# SH09-PWR2.net
KiCad netlist of a schematic drawn in Altium Designer
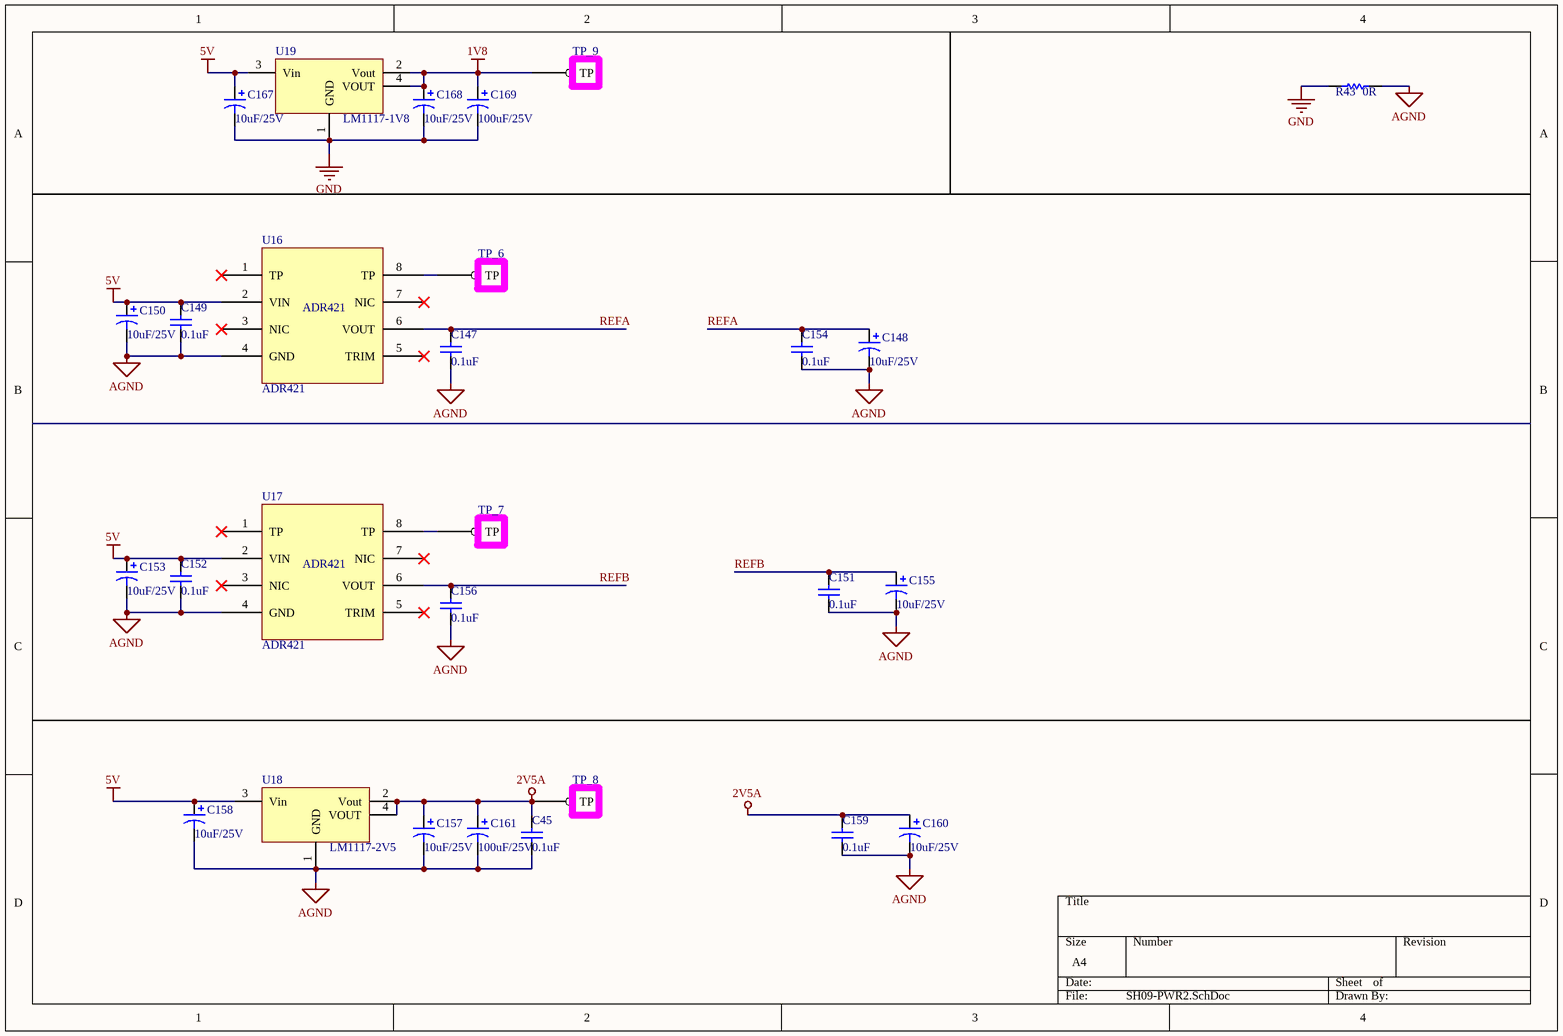
[diagram p0: SH09-PWR2.SchDoc]

(export (version "E")
  (design (tool "Eeschema 10.0.6"))
  (components
    (comp (ref "C45")
      (value "0.1uF")
      (footprint "1608[0603]")
      (description "Capacitor")
      (fields (field (name "Comment") "Cap,0.1uF/0603") (field (name "PUBLISHER") "Altium Limited"))
      (libsource (lib "Miscellaneous Devices") (part "Cap"))
    )
    (comp (ref "C147")
      (value "0.1uF")
      (footprint "1608[0603]")
      (description "Capacitor")
      (fields (field (name "Comment") "Cap,0.1uF/0603") (field (name "PUBLISHER") "Altium Limited"))
      (libsource (lib "Miscellaneous Devices") (part "Cap"))
    )
    (comp (ref "C148")
      (value "10uF/25V")
      (footprint "1206[3216]")
      (description "Polarized Capacitor (Radial)")
      (fields (field (name "Comment") "Cap Pol,10uF/25V,1206") (field (name "PUBLISHER") "Altium Limited"))
      (libsource (lib "Miscellaneous Devices") (part "Cap Pol1"))
    )
    (comp (ref "C149")
      (value "0.1uF")
      (footprint "1608[0603]")
      (description "Capacitor")
      (fields (field (name "Comment") "Cap,0.1uF/0603") (field (name "PUBLISHER") "Altium Limited"))
      (libsource (lib "Miscellaneous Devices") (part "Cap"))
    )
    (comp (ref "C150")
      (value "10uF/25V")
      (footprint "1206[3216]")
      (description "Polarized Capacitor (Radial)")
      (fields (field (name "Comment") "Cap Pol,10uF/25V,1206") (field (name "PUBLISHER") "Altium Limited"))
      (libsource (lib "Miscellaneous Devices") (part "Cap Pol1"))
    )
    (comp (ref "C151")
      (value "0.1uF")
      (footprint "1608[0603]")
      (description "Capacitor")
      (fields (field (name "Comment") "Cap,0.1uF/0603") (field (name "PUBLISHER") "Altium Limited"))
      (libsource (lib "Miscellaneous Devices") (part "Cap"))
    )
    (comp (ref "C152")
      (value "0.1uF")
      (footprint "1608[0603]")
      (description "Capacitor")
      (fields (field (name "Comment") "Cap,0.1uF/0603") (field (name "PUBLISHER") "Altium Limited"))
      (libsource (lib "Miscellaneous Devices") (part "Cap"))
    )
    (comp (ref "C153")
      (value "10uF/25V")
      (footprint "1206[3216]")
      (description "Polarized Capacitor (Radial)")
      (fields (field (name "Comment") "Cap Pol,10uF/25V,1206") (field (name "PUBLISHER") "Altium Limited"))
      (libsource (lib "Miscellaneous Devices") (part "Cap Pol1"))
    )
    (comp (ref "C154")
      (value "0.1uF")
      (footprint "1608[0603]")
      (description "Capacitor")
      (fields (field (name "Comment") "Cap,0.1uF/0603") (field (name "PUBLISHER") "Altium Limited"))
      (libsource (lib "Miscellaneous Devices") (part "Cap"))
    )
    (comp (ref "C155")
      (value "10uF/25V")
      (footprint "1206[3216]")
      (description "Polarized Capacitor (Radial)")
      (fields (field (name "Comment") "Cap Pol,10uF/25V,1206") (field (name "PUBLISHER") "Altium Limited"))
      (libsource (lib "Miscellaneous Devices") (part "Cap Pol1"))
    )
    (comp (ref "C156")
      (value "0.1uF")
      (footprint "1608[0603]")
      (description "Capacitor")
      (fields (field (name "Comment") "Cap,0.1uF/0603") (field (name "PUBLISHER") "Altium Limited"))
      (libsource (lib "Miscellaneous Devices") (part "Cap"))
    )
    (comp (ref "C157")
      (value "10uF/25V")
      (footprint "1206[3216]")
      (description "Polarized Capacitor (Radial)")
      (fields (field (name "Comment") "Cap Pol,10uF/25V,1206") (field (name "PUBLISHER") "Altium Limited"))
      (libsource (lib "Miscellaneous Devices") (part "Cap Pol1"))
    )
    (comp (ref "C158")
      (value "10uF/25V")
      (footprint "1206[3216]")
      (description "Polarized Capacitor (Radial)")
      (fields (field (name "Comment") "Cap Pol,10uF/25V,1206") (field (name "PUBLISHER") "Altium Limited"))
      (libsource (lib "Miscellaneous Devices") (part "Cap Pol1"))
    )
    (comp (ref "C159")
      (value "0.1uF")
      (footprint "1608[0603]")
      (description "Capacitor")
      (fields (field (name "Comment") "Cap,0.1uF/0603") (field (name "PUBLISHER") "Altium Limited"))
      (libsource (lib "Miscellaneous Devices") (part "Cap"))
    )
    (comp (ref "C160")
      (value "10uF/25V")
      (footprint "1206[3216]")
      (description "Polarized Capacitor (Radial)")
      (fields (field (name "Comment") "Cap Pol,10uF/25V,1206") (field (name "PUBLISHER") "Altium Limited"))
      (libsource (lib "Miscellaneous Devices") (part "Cap Pol1"))
    )
    (comp (ref "C161")
      (value "100uF/25V")
      (footprint "1210[3528]")
      (description "Polarized Capacitor (Radial)")
      (fields (field (name "Comment") "Cap Pol,100uF/25V,1210") (field (name "PUBLISHER") "Altium Limited"))
      (libsource (lib "Miscellaneous Devices") (part "Cap Pol1"))
    )
    (comp (ref "C167")
      (value "10uF/25V")
      (footprint "1206[3216]")
      (description "Polarized Capacitor (Radial)")
      (fields (field (name "Comment") "Cap Pol,10uF/25V,1206") (field (name "PUBLISHER") "Altium Limited"))
      (libsource (lib "Miscellaneous Devices") (part "Cap Pol1"))
    )
    (comp (ref "C168")
      (value "10uF/25V")
      (footprint "1206[3216]")
      (description "Polarized Capacitor (Radial)")
      (fields (field (name "Comment") "Cap Pol,10uF/25V,1206") (field (name "PUBLISHER") "Altium Limited"))
      (libsource (lib "Miscellaneous Devices") (part "Cap Pol1"))
    )
    (comp (ref "C169")
      (value "100uF/25V")
      (footprint "1210[3528]")
      (description "Polarized Capacitor (Radial)")
      (fields (field (name "Comment") "Cap Pol,100uF/25V,1210") (field (name "PUBLISHER") "Altium Limited"))
      (libsource (lib "Miscellaneous Devices") (part "Cap Pol1"))
    )
    (comp (ref "R43")
      (value "0R")
      (footprint "Laser-LiuXin:2012[0805]")
      (description "Resistor")
      (fields (field (name "Comment") "Res,0R/0805") (field (name "PUBLISHER") "Altium Limited"))
      (libsource (lib "Miscellaneous Devices") (part "Res1"))
    )
    (comp (ref "TP_6") (value "REFA") (footprint "MYTP") (libsource (lib "*") (part "TEST POINT_0")))
    (comp (ref "TP_7") (value "REFB") (footprint "MYTP") (libsource (lib "*") (part "TEST POINT_0")))
    (comp (ref "TP_8") (value "2V5") (footprint "MYTP") (libsource (lib "*") (part "TEST POINT_0")))
    (comp (ref "TP_9") (value "1V8") (footprint "MYTP") (libsource (lib "*") (part "TEST POINT_0")))
    (comp (ref "U16")
      (value "ADR421")
      (footprint "SOIC127P600X175-8N")
      (description "Ultraprecision Low Noise, 2.048 V/2.500 V/  3.00 V/5.00 V XFET? Voltage References")
      (libsource (lib "Laser-LiuXin") (part "PWR_ADR421"))
    )
    (comp (ref "U17")
      (value "ADR421")
      (footprint "SOIC127P600X175-8N")
      (description "Ultraprecision Low Noise, 2.048 V/2.500 V/  3.00 V/5.00 V XFET? Voltage References")
      (libsource (lib "Laser-LiuXin") (part "PWR_ADR421"))
    )
    (comp (ref "U18")
      (value "LM1117-2V5")
      (footprint "SOT223P700X180-4N")
      (libsource (lib "Mylibrary") (part "VOLTREG"))
    )
    (comp (ref "U19")
      (value "LM1117-1V8")
      (footprint "SOT223P700X180-4N")
      (libsource (lib "Mylibrary") (part "VOLTREG"))
    )
  )
  (nets
    (net (code "1") (name "/REFA") (class "Default")
      (node (ref "C147") (pin "1") (pinfunction "1_1") (pintype "passive"))
      (node (ref "C148") (pin "1") (pinfunction "1_1") (pintype "passive"))
      (node (ref "C154") (pin "1") (pinfunction "1_1") (pintype "passive"))
      (node (ref "U16") (pin "6") (pinfunction "VOUT_6") (pintype "power_in"))
    )
    (net (code "2") (name "/REFB") (class "Default")
      (node (ref "C151") (pin "1") (pinfunction "1_1") (pintype "passive"))
      (node (ref "C155") (pin "1") (pinfunction "1_1") (pintype "passive"))
      (node (ref "C156") (pin "1") (pinfunction "1_1") (pintype "passive"))
      (node (ref "U17") (pin "6") (pinfunction "VOUT_6") (pintype "power_in"))
    )
    (net (code "3") (name "1V8") (class "Default")
      (node (ref "C168") (pin "1") (pinfunction "1_1") (pintype "passive"))
      (node (ref "C169") (pin "1") (pinfunction "1_1") (pintype "passive"))
      (node (ref "TP_9") (pin "1") (pinfunction "TP_1") (pintype "passive"))
      (node (ref "U19") (pin "2") (pinfunction "Vout_2") (pintype "passive"))
      (node (ref "U19") (pin "4") (pinfunction "VOUT_4") (pintype "passive"))
    )
    (net (code "4") (name "2V5A") (class "Default")
      (node (ref "C157") (pin "1") (pinfunction "1_1") (pintype "passive"))
      (node (ref "C159") (pin "1") (pinfunction "1_1") (pintype "passive"))
      (node (ref "C160") (pin "1") (pinfunction "1_1") (pintype "passive"))
      (node (ref "C161") (pin "1") (pinfunction "1_1") (pintype "passive"))
      (node (ref "C45") (pin "1") (pinfunction "1_1") (pintype "passive"))
      (node (ref "TP_8") (pin "1") (pinfunction "TP_1") (pintype "passive"))
      (node (ref "U18") (pin "2") (pinfunction "Vout_2") (pintype "passive"))
      (node (ref "U18") (pin "4") (pinfunction "VOUT_4") (pintype "passive"))
    )
    (net (code "5") (name "5V") (class "Default")
      (node (ref "C149") (pin "1") (pinfunction "1_1") (pintype "passive"))
      (node (ref "C150") (pin "1") (pinfunction "1_1") (pintype "passive"))
      (node (ref "C152") (pin "1") (pinfunction "1_1") (pintype "passive"))
      (node (ref "C153") (pin "1") (pinfunction "1_1") (pintype "passive"))
      (node (ref "C158") (pin "1") (pinfunction "1_1") (pintype "passive"))
      (node (ref "C167") (pin "1") (pinfunction "1_1") (pintype "passive"))
      (node (ref "U16") (pin "2") (pinfunction "VIN_2") (pintype "power_in"))
      (node (ref "U17") (pin "2") (pinfunction "VIN_2") (pintype "power_in"))
      (node (ref "U18") (pin "3") (pinfunction "Vin_3") (pintype "passive"))
      (node (ref "U19") (pin "3") (pinfunction "Vin_3") (pintype "passive"))
    )
    (net (code "6") (name "AGND") (class "Default")
      (node (ref "C147") (pin "2") (pinfunction "2_2") (pintype "passive"))
      (node (ref "C148") (pin "2") (pinfunction "2_2") (pintype "passive"))
      (node (ref "C149") (pin "2") (pinfunction "2_2") (pintype "passive"))
      (node (ref "C150") (pin "2") (pinfunction "2_2") (pintype "passive"))
      (node (ref "C151") (pin "2") (pinfunction "2_2") (pintype "passive"))
      (node (ref "C152") (pin "2") (pinfunction "2_2") (pintype "passive"))
      (node (ref "C153") (pin "2") (pinfunction "2_2") (pintype "passive"))
      (node (ref "C154") (pin "2") (pinfunction "2_2") (pintype "passive"))
      (node (ref "C155") (pin "2") (pinfunction "2_2") (pintype "passive"))
      (node (ref "C156") (pin "2") (pinfunction "2_2") (pintype "passive"))
      (node (ref "C157") (pin "2") (pinfunction "2_2") (pintype "passive"))
      (node (ref "C158") (pin "2") (pinfunction "2_2") (pintype "passive"))
      (node (ref "C159") (pin "2") (pinfunction "2_2") (pintype "passive"))
      (node (ref "C160") (pin "2") (pinfunction "2_2") (pintype "passive"))
      (node (ref "C161") (pin "2") (pinfunction "2_2") (pintype "passive"))
      (node (ref "C45") (pin "2") (pinfunction "2_2") (pintype "passive"))
      (node (ref "R43") (pin "1") (pinfunction "1_1") (pintype "passive"))
      (node (ref "U16") (pin "4") (pinfunction "GND_4") (pintype "power_in"))
      (node (ref "U17") (pin "4") (pinfunction "GND_4") (pintype "power_in"))
      (node (ref "U18") (pin "1") (pinfunction "GND_1") (pintype "passive"))
    )
    (net (code "7") (name "GND") (class "Default")
      (node (ref "C167") (pin "2") (pinfunction "2_2") (pintype "passive"))
      (node (ref "C168") (pin "2") (pinfunction "2_2") (pintype "passive"))
      (node (ref "C169") (pin "2") (pinfunction "2_2") (pintype "passive"))
      (node (ref "R43") (pin "2") (pinfunction "2_2") (pintype "passive"))
      (node (ref "U19") (pin "1") (pinfunction "GND_1") (pintype "passive"))
    )
    (net (code "8") (name "Net-(TP_6-TP)") (class "Default")
      (node (ref "TP_6") (pin "1") (pinfunction "TP_1") (pintype "passive"))
      (node (ref "U16") (pin "8") (pinfunction "TP_8") (pintype "passive"))
    )
    (net (code "9") (name "Net-(TP_7-TP)") (class "Default")
      (node (ref "TP_7") (pin "1") (pinfunction "TP_1") (pintype "passive"))
      (node (ref "U17") (pin "8") (pinfunction "TP_8") (pintype "passive"))
    )
    (net (code "10") (name "unconnected-(U16-NIC-Pad3)") (class "Default")
      (node (ref "U16") (pin "3") (pinfunction "NIC_3") (pintype "passive+no_connect"))
    )
    (net (code "11") (name "unconnected-(U16-NIC-Pad7)") (class "Default")
      (node (ref "U16") (pin "7") (pinfunction "NIC_7") (pintype "passive+no_connect"))
    )
    (net (code "12") (name "unconnected-(U16-TP-Pad1)") (class "Default")
      (node (ref "U16") (pin "1") (pinfunction "TP_1") (pintype "power_in+no_connect"))
    )
    (net (code "13") (name "unconnected-(U16-TRIM-Pad5)") (class "Default")
      (node (ref "U16") (pin "5") (pinfunction "TRIM_5") (pintype "power_in+no_connect"))
    )
    (net (code "14") (name "unconnected-(U17-NIC-Pad3)") (class "Default")
      (node (ref "U17") (pin "3") (pinfunction "NIC_3") (pintype "passive+no_connect"))
    )
    (net (code "15") (name "unconnected-(U17-NIC-Pad7)") (class "Default")
      (node (ref "U17") (pin "7") (pinfunction "NIC_7") (pintype "passive+no_connect"))
    )
    (net (code "16") (name "unconnected-(U17-TP-Pad1)") (class "Default")
      (node (ref "U17") (pin "1") (pinfunction "TP_1") (pintype "power_in+no_connect"))
    )
    (net (code "17") (name "unconnected-(U17-TRIM-Pad5)") (class "Default")
      (node (ref "U17") (pin "5") (pinfunction "TRIM_5") (pintype "power_in+no_connect"))
    )
  )
)
